# vocore-evk.net
KiCad netlist of a schematic drawn in EAGLE
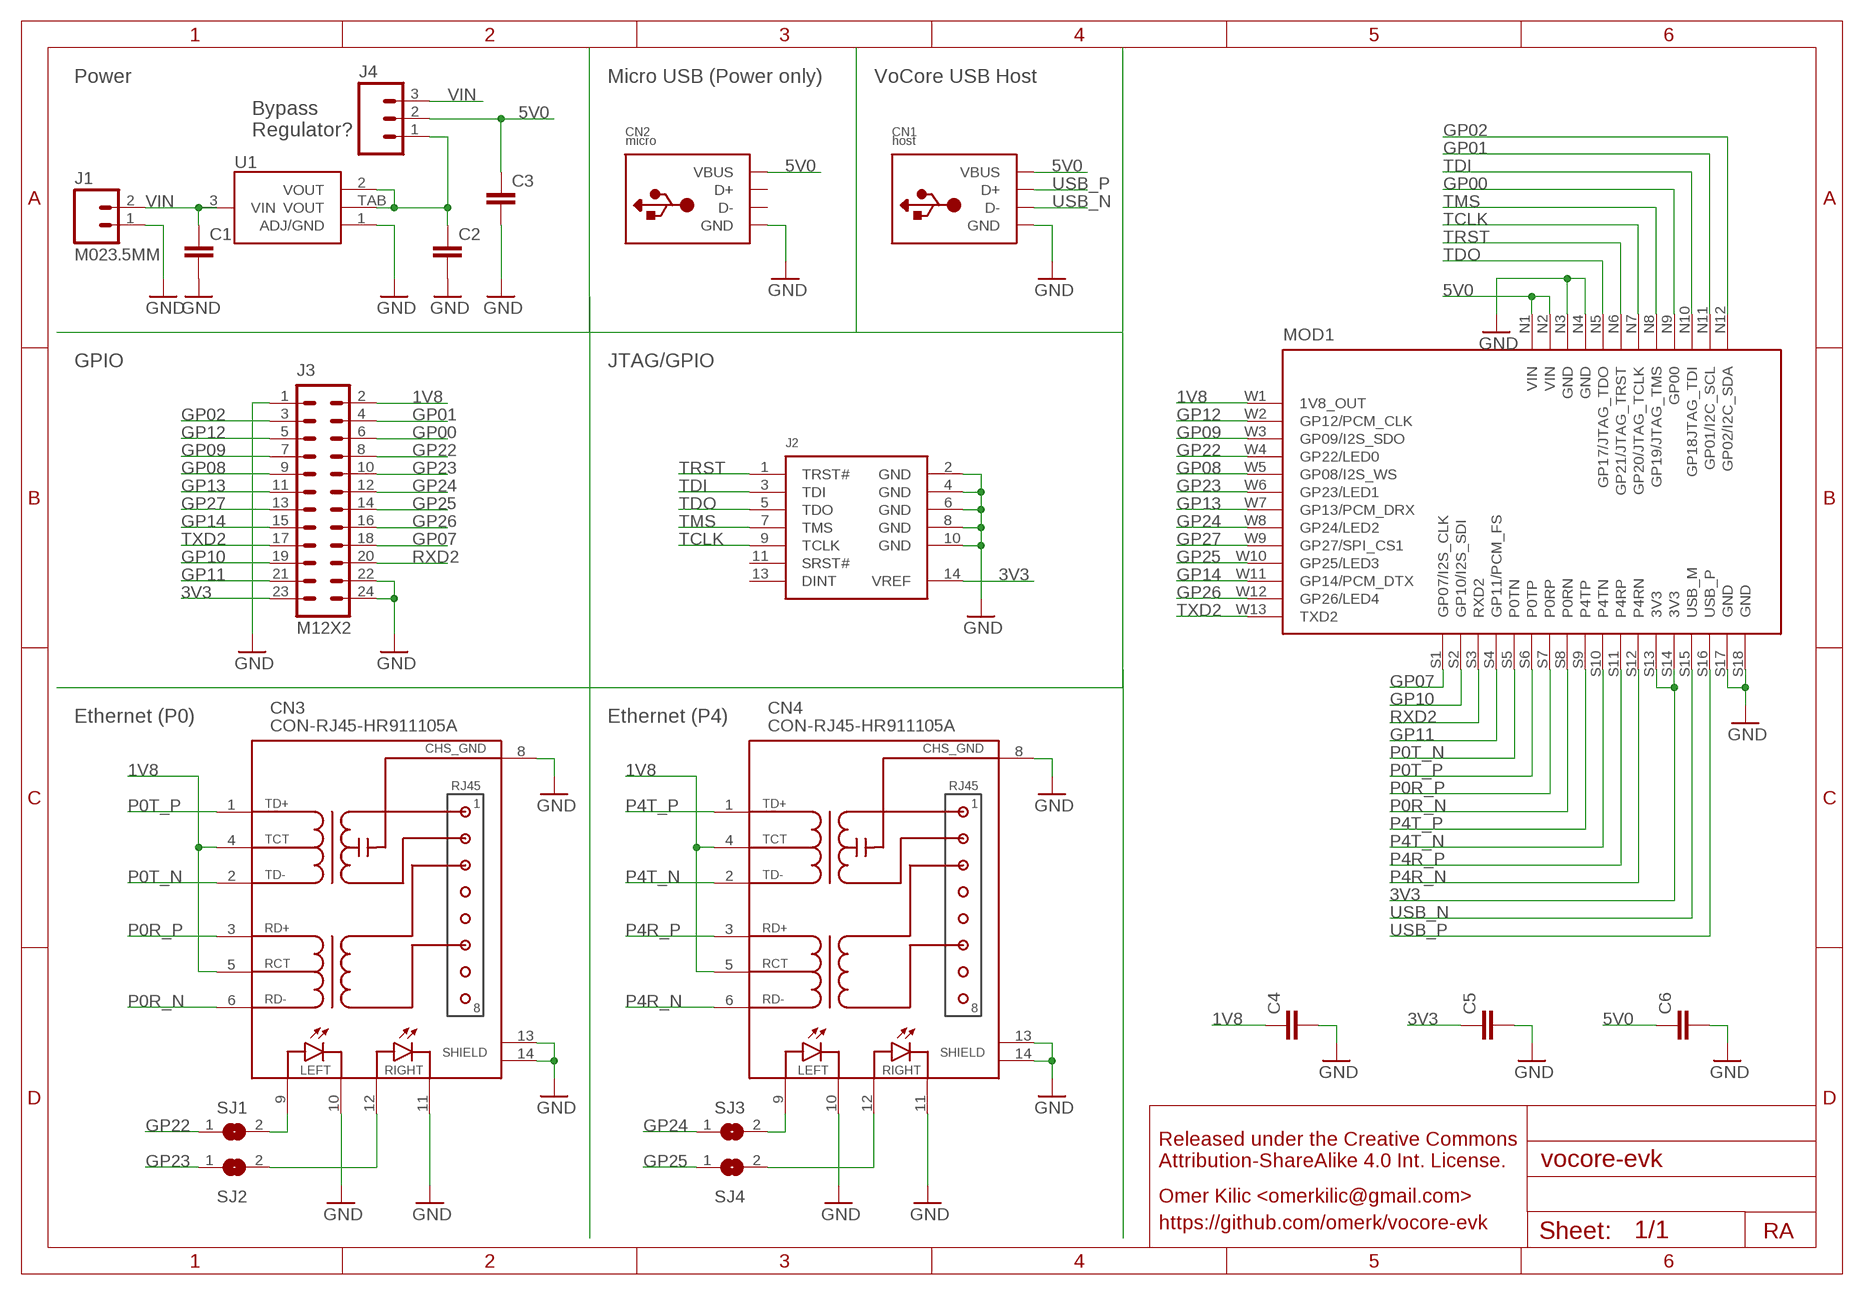
[diagram p0: schematic, sheet 1]

(export (version "E")
  (design (tool "Eeschema 10.0.6"))
  (components
    (comp (ref "C1")
      (value "C-EUC0805")
      (footprint "eagle-import:C0805")
      (libsource (lib "eagle-import") (part "C-EUC0805"))
    )
    (comp (ref "C2")
      (value "C-EUC0805")
      (footprint "eagle-import:C0805")
      (libsource (lib "eagle-import") (part "C-EUC0805"))
    )
    (comp (ref "C3")
      (value "C-EUC0805")
      (footprint "eagle-import:C0805")
      (libsource (lib "eagle-import") (part "C-EUC0805"))
    )
    (comp (ref "C4")
      (value "C-EUC0805")
      (footprint "eagle-import:C0805")
      (libsource (lib "eagle-import") (part "C-EUC0805"))
    )
    (comp (ref "C5")
      (value "C-EUC0805")
      (footprint "eagle-import:C0805")
      (libsource (lib "eagle-import") (part "C-EUC0805"))
    )
    (comp (ref "C6")
      (value "C-EUC0805")
      (footprint "eagle-import:C0805")
      (libsource (lib "eagle-import") (part "C-EUC0805"))
    )
    (comp (ref "CN1")
      (value "host")
      (footprint "eagle-import:USB-A-FEMALE-TH")
      (libsource (lib "eagle-import") (part "CON-USB-A-FEMALE-TH"))
    )
    (comp (ref "CN2")
      (value "micro")
      (footprint "eagle-import:USB-MOLEX-47346-0001")
      (libsource (lib "eagle-import") (part "CON-USB-MICRO-FEMALE-SMD"))
    )
    (comp (ref "CN3")
      (value "CON-RJ45-HR911105A")
      (footprint "eagle-import:HR911105A")
      (libsource (lib "eagle-import") (part "CON-RJ45-HR911105A"))
    )
    (comp (ref "CN4")
      (value "CON-RJ45-HR911105A")
      (footprint "eagle-import:HR911105A")
      (libsource (lib "eagle-import") (part "CON-RJ45-HR911105A"))
    )
    (comp (ref "J1")
      (value "M023.5MM")
      (footprint "eagle-import:SCREWTERMINAL-3.5MM-2")
      (libsource (lib "eagle-import") (part "M023.5MM"))
    )
    (comp (ref "J2")
      (value "EJTAG_MIPS")
      (footprint "eagle-import:M2X7")
      (libsource (lib "eagle-import") (part "EJTAG_MIPS"))
    )
    (comp (ref "J3")
      (value "M12X2")
      (footprint "eagle-import:M2X12")
      (libsource (lib "eagle-import") (part "M12X2"))
    )
    (comp (ref "J4")
      (value "M03PTH")
      (footprint "eagle-import:1X03")
      (libsource (lib "eagle-import") (part "M03PTH"))
    )
    (comp (ref "MOD1")
      (value "VOCORE_V10A")
      (footprint "eagle-import:VOCORE_V10A")
      (libsource (lib "eagle-import") (part "VOCORE_V10A"))
    )
    (comp (ref "SJ1") (value "SJ") (footprint "eagle-import:SJ") (libsource (lib "eagle-import") (part "SJ")))
    (comp (ref "SJ2") (value "SJ") (footprint "eagle-import:SJ") (libsource (lib "eagle-import") (part "SJ")))
    (comp (ref "SJ3") (value "SJ") (footprint "eagle-import:SJ") (libsource (lib "eagle-import") (part "SJ")))
    (comp (ref "SJ4") (value "SJ") (footprint "eagle-import:SJ") (libsource (lib "eagle-import") (part "SJ")))
    (comp (ref "U1")
      (value "LDO1117-SOT223")
      (footprint "eagle-import:SOT223-3L")
      (libsource (lib "eagle-import") (part "LDO1117-SOT223"))
    )
  )
  (nets
    (net (code "1") (name "/1V8") (class "Default")
      (node (ref "C4") (pin "1") (pinfunction "1_1") (pintype "passive"))
      (node (ref "CN3") (pin "4") (pinfunction "TCT_4") (pintype "bidirectional"))
      (node (ref "CN3") (pin "5") (pinfunction "RCT_5") (pintype "bidirectional"))
      (node (ref "CN4") (pin "4") (pinfunction "TCT_4") (pintype "bidirectional"))
      (node (ref "CN4") (pin "5") (pinfunction "RCT_5") (pintype "bidirectional"))
      (node (ref "J3") (pin "2") (pinfunction "2_2") (pintype "passive"))
      (node (ref "MOD1") (pin "W1") (pinfunction "1V8_OUT_W1") (pintype "power_in"))
    )
    (net (code "2") (name "/3V3") (class "Default")
      (node (ref "C5") (pin "1") (pinfunction "1_1") (pintype "passive"))
      (node (ref "J2") (pin "14") (pinfunction "VREF_14") (pintype "bidirectional"))
      (node (ref "J3") (pin "23") (pinfunction "23_23") (pintype "passive"))
      (node (ref "MOD1") (pin "S13") (pinfunction "3V3_S13") (pintype "bidirectional"))
      (node (ref "MOD1") (pin "S14") (pinfunction "3V3_S14") (pintype "bidirectional"))
    )
    (net (code "3") (name "/5V0") (class "Default")
      (node (ref "C3") (pin "1") (pinfunction "1_1") (pintype "passive"))
      (node (ref "C6") (pin "1") (pinfunction "1_1") (pintype "passive"))
      (node (ref "CN1") (pin "VBUS") (pinfunction "VBUS_VBUS") (pintype "power_in"))
      (node (ref "CN2") (pin "VBUS") (pinfunction "VBUS_VBUS") (pintype "power_in"))
      (node (ref "J4") (pin "2") (pinfunction "2_2") (pintype "passive"))
      (node (ref "MOD1") (pin "N1") (pinfunction "VIN_N1") (pintype "power_in"))
      (node (ref "MOD1") (pin "N2") (pinfunction "VIN_N2") (pintype "power_in"))
    )
    (net (code "4") (name "/GP00") (class "Default")
      (node (ref "J3") (pin "6") (pinfunction "6_6") (pintype "passive"))
      (node (ref "MOD1") (pin "N9") (pinfunction "GP00_N9") (pintype "bidirectional"))
    )
    (net (code "5") (name "/GP01") (class "Default")
      (node (ref "J3") (pin "4") (pinfunction "4_4") (pintype "passive"))
      (node (ref "MOD1") (pin "N11") (pinfunction "GP01/I2C_SCL_N11") (pintype "bidirectional"))
    )
    (net (code "6") (name "/GP02") (class "Default")
      (node (ref "J3") (pin "3") (pinfunction "3_3") (pintype "passive"))
      (node (ref "MOD1") (pin "N12") (pinfunction "GP02/I2C_SDA_N12") (pintype "bidirectional"))
    )
    (net (code "7") (name "/GP07") (class "Default")
      (node (ref "J3") (pin "18") (pinfunction "18_18") (pintype "passive"))
      (node (ref "MOD1") (pin "S1") (pinfunction "GP07/I2S_CLK_S1") (pintype "bidirectional"))
    )
    (net (code "8") (name "/GP08") (class "Default")
      (node (ref "J3") (pin "9") (pinfunction "9_9") (pintype "passive"))
      (node (ref "MOD1") (pin "W5") (pinfunction "GP08/I2S_WS_W5") (pintype "bidirectional"))
    )
    (net (code "9") (name "/GP09") (class "Default")
      (node (ref "J3") (pin "7") (pinfunction "7_7") (pintype "passive"))
      (node (ref "MOD1") (pin "W3") (pinfunction "GP09/I2S_SDO_W3") (pintype "bidirectional"))
    )
    (net (code "10") (name "/GP10") (class "Default")
      (node (ref "J3") (pin "19") (pinfunction "19_19") (pintype "passive"))
      (node (ref "MOD1") (pin "S2") (pinfunction "GP10/I2S_SDI_S2") (pintype "bidirectional"))
    )
    (net (code "11") (name "/GP11") (class "Default")
      (node (ref "J3") (pin "21") (pinfunction "21_21") (pintype "passive"))
      (node (ref "MOD1") (pin "S4") (pinfunction "GP11/PCM_FS_S4") (pintype "bidirectional"))
    )
    (net (code "12") (name "/GP12") (class "Default")
      (node (ref "J3") (pin "5") (pinfunction "5_5") (pintype "passive"))
      (node (ref "MOD1") (pin "W2") (pinfunction "GP12/PCM_CLK_W2") (pintype "bidirectional"))
    )
    (net (code "13") (name "/GP13") (class "Default")
      (node (ref "J3") (pin "11") (pinfunction "11_11") (pintype "passive"))
      (node (ref "MOD1") (pin "W7") (pinfunction "GP13/PCM_DRX_W7") (pintype "bidirectional"))
    )
    (net (code "14") (name "/GP14") (class "Default")
      (node (ref "J3") (pin "15") (pinfunction "15_15") (pintype "passive"))
      (node (ref "MOD1") (pin "W11") (pinfunction "GP14/PCM_DTX_W11") (pintype "bidirectional"))
    )
    (net (code "15") (name "/GP22") (class "Default")
      (node (ref "J3") (pin "8") (pinfunction "8_8") (pintype "passive"))
      (node (ref "MOD1") (pin "W4") (pinfunction "GP22/LED0_W4") (pintype "bidirectional"))
      (node (ref "SJ1") (pin "1") (pinfunction "1_1") (pintype "passive"))
    )
    (net (code "16") (name "/GP23") (class "Default")
      (node (ref "J3") (pin "10") (pinfunction "10_10") (pintype "passive"))
      (node (ref "MOD1") (pin "W6") (pinfunction "GP23/LED1_W6") (pintype "bidirectional"))
      (node (ref "SJ2") (pin "1") (pinfunction "1_1") (pintype "passive"))
    )
    (net (code "17") (name "/GP24") (class "Default")
      (node (ref "J3") (pin "12") (pinfunction "12_12") (pintype "passive"))
      (node (ref "MOD1") (pin "W8") (pinfunction "GP24/LED2_W8") (pintype "bidirectional"))
      (node (ref "SJ3") (pin "1") (pinfunction "1_1") (pintype "passive"))
    )
    (net (code "18") (name "/GP25") (class "Default")
      (node (ref "J3") (pin "14") (pinfunction "14_14") (pintype "passive"))
      (node (ref "MOD1") (pin "W10") (pinfunction "GP25/LED3_W10") (pintype "bidirectional"))
      (node (ref "SJ4") (pin "1") (pinfunction "1_1") (pintype "passive"))
    )
    (net (code "19") (name "/GP26") (class "Default")
      (node (ref "J3") (pin "16") (pinfunction "16_16") (pintype "passive"))
      (node (ref "MOD1") (pin "W12") (pinfunction "GP26/LED4_W12") (pintype "bidirectional"))
    )
    (net (code "20") (name "/GP27") (class "Default")
      (node (ref "J3") (pin "13") (pinfunction "13_13") (pintype "passive"))
      (node (ref "MOD1") (pin "W9") (pinfunction "GP27/SPI_CS1_W9") (pintype "bidirectional"))
    )
    (net (code "21") (name "/P0R_N") (class "Default")
      (node (ref "CN3") (pin "6") (pinfunction "RD-_6") (pintype "bidirectional"))
      (node (ref "MOD1") (pin "S8") (pinfunction "P0RN_S8") (pintype "bidirectional"))
    )
    (net (code "22") (name "/P0R_P") (class "Default")
      (node (ref "CN3") (pin "3") (pinfunction "RD+_3") (pintype "bidirectional"))
      (node (ref "MOD1") (pin "S7") (pinfunction "P0RP_S7") (pintype "bidirectional"))
    )
    (net (code "23") (name "/P0T_N") (class "Default")
      (node (ref "CN3") (pin "2") (pinfunction "TD-_2") (pintype "bidirectional"))
      (node (ref "MOD1") (pin "S5") (pinfunction "P0TN_S5") (pintype "bidirectional"))
    )
    (net (code "24") (name "/P0T_P") (class "Default")
      (node (ref "CN3") (pin "1") (pinfunction "TD+_1") (pintype "bidirectional"))
      (node (ref "MOD1") (pin "S6") (pinfunction "P0TP_S6") (pintype "bidirectional"))
    )
    (net (code "25") (name "/P4R_N") (class "Default")
      (node (ref "CN4") (pin "6") (pinfunction "RD-_6") (pintype "bidirectional"))
      (node (ref "MOD1") (pin "S12") (pinfunction "P4RN_S12") (pintype "bidirectional"))
    )
    (net (code "26") (name "/P4R_P") (class "Default")
      (node (ref "CN4") (pin "3") (pinfunction "RD+_3") (pintype "bidirectional"))
      (node (ref "MOD1") (pin "S11") (pinfunction "P4RP_S11") (pintype "bidirectional"))
    )
    (net (code "27") (name "/P4T_N") (class "Default")
      (node (ref "CN4") (pin "2") (pinfunction "TD-_2") (pintype "bidirectional"))
      (node (ref "MOD1") (pin "S10") (pinfunction "P4TN_S10") (pintype "bidirectional"))
    )
    (net (code "28") (name "/P4T_P") (class "Default")
      (node (ref "CN4") (pin "1") (pinfunction "TD+_1") (pintype "bidirectional"))
      (node (ref "MOD1") (pin "S9") (pinfunction "P4TP_S9") (pintype "bidirectional"))
    )
    (net (code "29") (name "/RXD2") (class "Default")
      (node (ref "J3") (pin "20") (pinfunction "20_20") (pintype "passive"))
      (node (ref "MOD1") (pin "S3") (pinfunction "RXD2_S3") (pintype "bidirectional"))
    )
    (net (code "30") (name "/TCLK") (class "Default")
      (node (ref "J2") (pin "9") (pinfunction "TCLK_9") (pintype "bidirectional"))
      (node (ref "MOD1") (pin "N7") (pinfunction "GP20/JTAG_TCLK_N7") (pintype "bidirectional"))
    )
    (net (code "31") (name "/TDI") (class "Default")
      (node (ref "J2") (pin "3") (pinfunction "TDI_3") (pintype "bidirectional"))
      (node (ref "MOD1") (pin "N10") (pinfunction "GP18JTAG_TDI_N10") (pintype "bidirectional"))
    )
    (net (code "32") (name "/TDO") (class "Default")
      (node (ref "J2") (pin "5") (pinfunction "TDO_5") (pintype "bidirectional"))
      (node (ref "MOD1") (pin "N5") (pinfunction "GP17/JTAG_TDO_N5") (pintype "bidirectional"))
    )
    (net (code "33") (name "/TMS") (class "Default")
      (node (ref "J2") (pin "7") (pinfunction "TMS_7") (pintype "bidirectional"))
      (node (ref "MOD1") (pin "N8") (pinfunction "GP19/JTAG_TMS_N8") (pintype "bidirectional"))
    )
    (net (code "34") (name "/TRST") (class "Default")
      (node (ref "J2") (pin "1") (pinfunction "TRST#_1") (pintype "bidirectional"))
      (node (ref "MOD1") (pin "N6") (pinfunction "GP21/JTAG_TRST_N6") (pintype "bidirectional"))
    )
    (net (code "35") (name "/TXD2") (class "Default")
      (node (ref "J3") (pin "17") (pinfunction "17_17") (pintype "passive"))
      (node (ref "MOD1") (pin "W13") (pinfunction "TXD2_W13") (pintype "bidirectional"))
    )
    (net (code "36") (name "/USB_N") (class "Default")
      (node (ref "CN1") (pin "D-") (pinfunction "D-_D-") (pintype "bidirectional"))
      (node (ref "MOD1") (pin "S15") (pinfunction "USB_M_S15") (pintype "bidirectional"))
    )
    (net (code "37") (name "/USB_P") (class "Default")
      (node (ref "CN1") (pin "D+") (pinfunction "D+_D+") (pintype "bidirectional"))
      (node (ref "MOD1") (pin "S16") (pinfunction "USB_P_S16") (pintype "bidirectional"))
    )
    (net (code "38") (name "/VIN") (class "Default")
      (node (ref "C1") (pin "1") (pinfunction "1_1") (pintype "passive"))
      (node (ref "J1") (pin "2") (pinfunction "2_2") (pintype "passive"))
      (node (ref "J4") (pin "3") (pinfunction "3_3") (pintype "passive"))
      (node (ref "U1") (pin "3") (pinfunction "VIN_3") (pintype "passive"))
    )
    (net (code "39") (name "GND") (class "Default")
      (node (ref "C1") (pin "2") (pinfunction "2_2") (pintype "passive"))
      (node (ref "C2") (pin "2") (pinfunction "2_2") (pintype "passive"))
      (node (ref "C3") (pin "2") (pinfunction "2_2") (pintype "passive"))
      (node (ref "C4") (pin "2") (pinfunction "2_2") (pintype "passive"))
      (node (ref "C5") (pin "2") (pinfunction "2_2") (pintype "passive"))
      (node (ref "C6") (pin "2") (pinfunction "2_2") (pintype "passive"))
      (node (ref "CN1") (pin "GND") (pinfunction "GND_GND") (pintype "power_in"))
      (node (ref "CN2") (pin "GND") (pinfunction "GND_GND") (pintype "power_in"))
      (node (ref "CN3") (pin "10") (pinfunction "LEFT_GRN_LED_K_10") (pintype "bidirectional"))
      (node (ref "CN3") (pin "11") (pinfunction "RIGHT_YLW_LED_K_11") (pintype "bidirectional"))
      (node (ref "CN3") (pin "13") (pinfunction "SHIELD_13") (pintype "bidirectional"))
      (node (ref "CN3") (pin "14") (pinfunction "SHIELD_14") (pintype "bidirectional"))
      (node (ref "CN3") (pin "8") (pinfunction "CHS_GND_8") (pintype "bidirectional"))
      (node (ref "CN4") (pin "10") (pinfunction "LEFT_GRN_LED_K_10") (pintype "bidirectional"))
      (node (ref "CN4") (pin "11") (pinfunction "RIGHT_YLW_LED_K_11") (pintype "bidirectional"))
      (node (ref "CN4") (pin "13") (pinfunction "SHIELD_13") (pintype "bidirectional"))
      (node (ref "CN4") (pin "14") (pinfunction "SHIELD_14") (pintype "bidirectional"))
      (node (ref "CN4") (pin "8") (pinfunction "CHS_GND_8") (pintype "bidirectional"))
      (node (ref "J1") (pin "1") (pinfunction "1_1") (pintype "passive"))
      (node (ref "J2") (pin "10") (pinfunction "GND_10") (pintype "bidirectional"))
      (node (ref "J2") (pin "2") (pinfunction "GND_2") (pintype "bidirectional"))
      (node (ref "J2") (pin "4") (pinfunction "GND_4") (pintype "bidirectional"))
      (node (ref "J2") (pin "6") (pinfunction "GND_6") (pintype "bidirectional"))
      (node (ref "J2") (pin "8") (pinfunction "GND_8") (pintype "bidirectional"))
      (node (ref "J3") (pin "1") (pinfunction "1_1") (pintype "passive"))
      (node (ref "J3") (pin "22") (pinfunction "22_22") (pintype "passive"))
      (node (ref "J3") (pin "24") (pinfunction "24_24") (pintype "passive"))
      (node (ref "MOD1") (pin "N3") (pinfunction "GND_N3") (pintype "power_in"))
      (node (ref "MOD1") (pin "N4") (pinfunction "GND_N4") (pintype "power_in"))
      (node (ref "MOD1") (pin "S17") (pinfunction "GND_S17") (pintype "power_in"))
      (node (ref "MOD1") (pin "S18") (pinfunction "GND_S18") (pintype "power_in"))
      (node (ref "U1") (pin "1") (pinfunction "ADJ/GND_1") (pintype "passive"))
    )
    (net (code "40") (name "Net-(C2-Pad1)") (class "Default")
      (node (ref "C2") (pin "1") (pinfunction "1_1") (pintype "passive"))
      (node (ref "J4") (pin "1") (pinfunction "1_1") (pintype "passive"))
      (node (ref "U1") (pin "2") (pinfunction "VOUT_2") (pintype "passive"))
      (node (ref "U1") (pin "TAB") (pinfunction "VOUT_TAB") (pintype "passive"))
    )
    (net (code "41") (name "Net-(CN3-LEFT_GRN_LED_A)") (class "Default")
      (node (ref "CN3") (pin "9") (pinfunction "LEFT_GRN_LED_A_9") (pintype "bidirectional"))
      (node (ref "SJ1") (pin "2") (pinfunction "2_2") (pintype "passive"))
    )
    (net (code "42") (name "Net-(CN3-RIGHT_YLW_LED_A)") (class "Default")
      (node (ref "CN3") (pin "12") (pinfunction "RIGHT_YLW_LED_A_12") (pintype "bidirectional"))
      (node (ref "SJ2") (pin "2") (pinfunction "2_2") (pintype "passive"))
    )
    (net (code "43") (name "Net-(CN4-LEFT_GRN_LED_A)") (class "Default")
      (node (ref "CN4") (pin "9") (pinfunction "LEFT_GRN_LED_A_9") (pintype "bidirectional"))
      (node (ref "SJ3") (pin "2") (pinfunction "2_2") (pintype "passive"))
    )
    (net (code "44") (name "Net-(CN4-RIGHT_YLW_LED_A)") (class "Default")
      (node (ref "CN4") (pin "12") (pinfunction "RIGHT_YLW_LED_A_12") (pintype "bidirectional"))
      (node (ref "SJ4") (pin "2") (pinfunction "2_2") (pintype "passive"))
    )
    (net (code "45") (name "unconnected-(CN2-PadD+)") (class "Default")
      (node (ref "CN2") (pin "D+") (pinfunction "D+_D+") (pintype "bidirectional"))
    )
    (net (code "46") (name "unconnected-(CN2-PadD-)") (class "Default")
      (node (ref "CN2") (pin "D-") (pinfunction "D-_D-") (pintype "bidirectional"))
    )
    (net (code "47") (name "unconnected-(J2-DINT-Pad13)") (class "Default")
      (node (ref "J2") (pin "13") (pinfunction "DINT_13") (pintype "bidirectional"))
    )
    (net (code "48") (name "unconnected-(J2-SRST#-Pad11)") (class "Default")
      (node (ref "J2") (pin "11") (pinfunction "SRST#_11") (pintype "bidirectional"))
    )
  )
)
